# AFE_D.net
KiCad netlist of a schematic drawn in Altium Designer
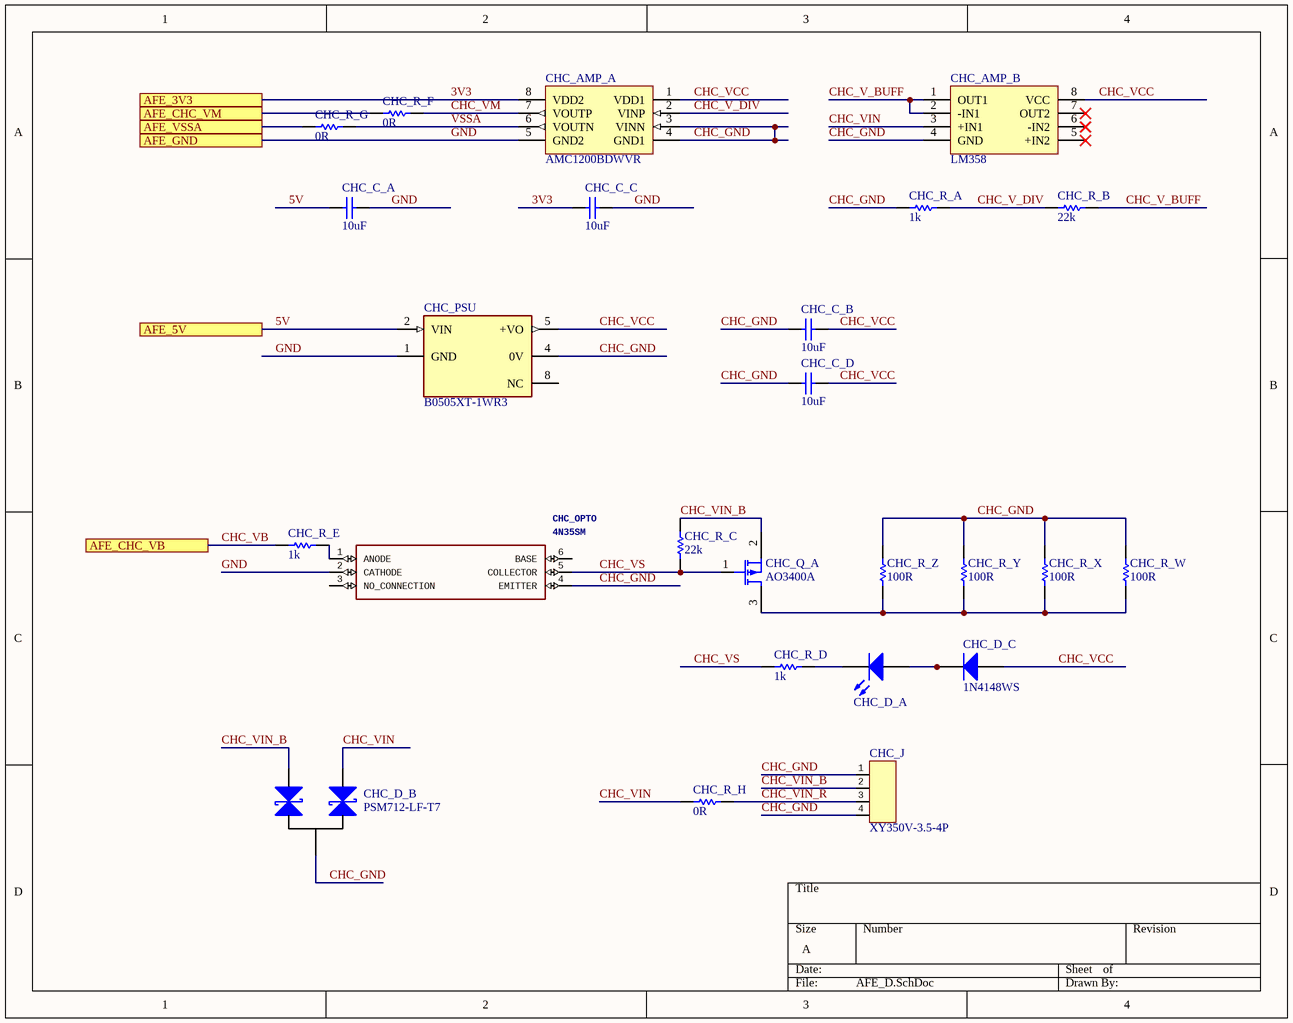
[diagram p0: AFE_D.SchDoc]

(export (version "E")
  (design (tool "Eeschema 10.0.6"))
  (components
    (comp (ref "CHC_AMP_A")
      (value "AMC1200BDWVR")
      (footprint "FOOTPRINTS:SOIC-8-P1.27-W7.5")
      (description "U - IC - 100KHz ISOLATION AMPLIFIER")
      (fields (field (name "LCSC PART #") "C79905"))
      (libsource (lib "JLC_PCB") (part "AMC1200BDWVR"))
    )
    (comp (ref "CHC_AMP_B")
      (value "LM358")
      (footprint "FOOTPRINTS:SOIC-8-P1.27-W3.5")
      (description "U - IC - OP AMP (DUAL)")
      (fields (field (name "LCSC PART #") "C63813"))
      (libsource (lib "JLC_PCB") (part "LMV358IDR"))
    )
    (comp (ref "CHC_C_A")
      (value "10uF")
      (footprint "C_0603")
      (description "C - CAPACITOR - MLCC - 10uF - 25V - 0603")
      (fields (field (name "LCSC PART #") "C96446") (field (name "Comment") "CL10A106MA8NRNC"))
      (libsource (lib "JLC_PCB") (part "CL10A106MA8NRNC"))
    )
    (comp (ref "CHC_C_B")
      (value "10uF")
      (footprint "C_0603")
      (description "C - CAPACITOR - MLCC - 10uF - 25V - 0603")
      (fields (field (name "LCSC PART #") "C96446") (field (name "Comment") "CL10A106MA8NRNC"))
      (libsource (lib "JLC_PCB") (part "CL10A106MA8NRNC"))
    )
    (comp (ref "CHC_C_C")
      (value "10uF")
      (footprint "C_0603")
      (description "C - CAPACITOR - MLCC - 10uF - 25V - 0603")
      (fields (field (name "LCSC PART #") "C96446") (field (name "Comment") "CL10A106MA8NRNC"))
      (libsource (lib "JLC_PCB") (part "CL10A106MA8NRNC"))
    )
    (comp (ref "CHC_C_D")
      (value "10uF")
      (footprint "C_0603")
      (description "C - CAPACITOR - MLCC - 10uF - 25V - 0603")
      (fields (field (name "LCSC PART #") "C96446") (field (name "Comment") "CL10A106MA8NRNC"))
      (libsource (lib "JLC_PCB") (part "CL10A106MA8NRNC"))
    )
    (comp (ref "CHC_D_A")
      (value "KT-0603R")
      (footprint "D_0603")
      (description "D - LED - 0603 - Red")
      (fields (field (name "LCSC PART #") "C2286"))
      (libsource (lib "JLC_PCB") (part "KT-0603R"))
    )
    (comp (ref "CHC_D_B")
      (value "PSM712-LF-T7")
      (footprint "TO-236AB")
      (description "D - DIODE - TVS x2 - 7.2V")
      (fields (field (name "LCSC PART #") "C32677"))
      (libsource (lib "JLC_PCB") (part "PSM712-LF-T7"))
    )
    (comp (ref "CHC_D_C")
      (value "1N4148WS")
      (footprint "SOD-323")
      (description "D - DIODE - FAST TRR - 100V - 150mA - 4ns")
      (fields (field (name "LCSC PART #") "C2128"))
      (libsource (lib "JLC_PCB") (part "1N4148WS"))
    )
    (comp (ref "CHC_J")
      (value "XY350V-3.5-4P")
      (footprint "XY350V-3.5-4P")
      (description "J - JACK - TERMINAL - 4P - RIGHT - MALE")
      (fields (field (name "LCSC PART #") "C557656"))
      (libsource (lib "JLC_PCB") (part "XY350V-3.5-4P"))
    )
    (comp (ref "CHC_OPTO")
      (value "4N35SM")
      (footprint "SOT254P916X508-6N")
      (description "Q - OPTOCOUPLER - 4170 V - 100% CTR")
      (fields (field (name "LCSC PART #") "C258228"))
      (libsource (lib "JLC_PCB") (part "4N35SM"))
    )
    (comp (ref "CHC_PSU")
      (value "B0505XT-1WR3")
      (footprint "CONV_B0512XT-1WR3")
      (description "T - Isolated Module DC DC Converter 5 -> 5V 200mA - DIP")
      (fields (field (name "LCSC PART #") "C19188495") (field (name "MF") "EVISUN"))
      (libsource (lib "JLC_PCB") (part "B0505XT-1WR3"))
    )
    (comp (ref "CHC_Q_A")
      (value "AO3400A")
      (footprint "TO-236AB")
      (description "Q - TRANSISTOR - MOSFET (P) - 20V - 3.4A - 0.26 Ohm")
      (fields (field (name "LCSC PART #") "C20917"))
      (libsource (lib "JLC_PCB") (part "AO3400A"))
    )
    (comp (ref "CHC_R_A")
      (value "1k")
      (footprint "R_0603")
      (description "R - RESISTOR - SMD - 1k - 1% - 0603")
      (fields (field (name "LCSC PART #") "C21190") (field (name "Comment") "0603WAF1001T5E"))
      (libsource (lib "JLC_PCB") (part "0603WAF1001T5E"))
    )
    (comp (ref "CHC_R_B")
      (value "22k")
      (footprint "R_0603")
      (description "R - RESISTOR - SMD - 22k - 1% - 0603")
      (fields (field (name "LCSC PART #") "C31850") (field (name "Comment") "0603WAF2202T5E"))
      (libsource (lib "JLC_PCB") (part "0603WAF2202T5E"))
    )
    (comp (ref "CHC_R_C")
      (value "22k")
      (footprint "R_0603")
      (description "R - RESISTOR - SMD - 22k - 1% - 0603")
      (fields (field (name "LCSC PART #") "C31850") (field (name "Comment") "0603WAF2202T5E"))
      (libsource (lib "JLC_PCB") (part "0603WAF2202T5E"))
    )
    (comp (ref "CHC_R_D")
      (value "1k")
      (footprint "R_0603")
      (description "R - RESISTOR - SMD - 1k - 1% - 0603")
      (fields (field (name "LCSC PART #") "C21190") (field (name "Comment") "0603WAF1001T5E"))
      (libsource (lib "JLC_PCB") (part "0603WAF1001T5E"))
    )
    (comp (ref "CHC_R_E")
      (value "1k")
      (footprint "R_0603")
      (description "R - RESISTOR - SMD - 1k - 1% - 0603")
      (fields (field (name "LCSC PART #") "C21190") (field (name "Comment") "0603WAF1001T5E"))
      (libsource (lib "JLC_PCB") (part "0603WAF1001T5E"))
    )
    (comp (ref "CHC_R_F")
      (value "0R")
      (footprint "R_0603")
      (description "R - RESISTOR - SMD - 0R - 1% - 0603")
      (fields (field (name "LCSC PART #") "C21189") (field (name "Comment") "0603WAF0000T5E"))
      (libsource (lib "JLC_PCB") (part "0603WAF0000T5E"))
    )
    (comp (ref "CHC_R_G")
      (value "0R")
      (footprint "R_0603")
      (description "R - RESISTOR - SMD - 0R - 1% - 0603")
      (fields (field (name "LCSC PART #") "C21189") (field (name "Comment") "0603WAF0000T5E"))
      (libsource (lib "JLC_PCB") (part "0603WAF0000T5E"))
    )
    (comp (ref "CHC_R_H")
      (value "0R")
      (footprint "R_0603")
      (description "R - RESISTOR - SMD - 0R - 1% - 0603")
      (fields (field (name "LCSC PART #") "C21189") (field (name "Comment") "0603WAF0000T5E"))
      (libsource (lib "JLC_PCB") (part "0603WAF0000T5E"))
    )
    (comp (ref "CHC_R_W")
      (value "100R")
      (footprint "R_1206")
      (description "R - RESISTOR - SMD - 100R - 1% - 1206")
      (fields (field (name "LCSC PART #") "C17901") (field (name "Comment") "1206W4F1000T5E"))
      (libsource (lib "JLC_PCB") (part "1206W4F1000T5E"))
    )
    (comp (ref "CHC_R_X")
      (value "100R")
      (footprint "R_1206")
      (description "R - RESISTOR - SMD - 100R - 1% - 1206")
      (fields (field (name "LCSC PART #") "C17901") (field (name "Comment") "1206W4F1000T5E"))
      (libsource (lib "JLC_PCB") (part "1206W4F1000T5E"))
    )
    (comp (ref "CHC_R_Y")
      (value "100R")
      (footprint "R_1206")
      (description "R - RESISTOR - SMD - 100R - 1% - 1206")
      (fields (field (name "LCSC PART #") "C17901") (field (name "Comment") "1206W4F1000T5E"))
      (libsource (lib "JLC_PCB") (part "1206W4F1000T5E"))
    )
    (comp (ref "CHC_R_Z")
      (value "100R")
      (footprint "R_1206")
      (description "R - RESISTOR - SMD - 100R - 1% - 1206")
      (fields (field (name "LCSC PART #") "C17901") (field (name "Comment") "1206W4F1000T5E"))
      (libsource (lib "JLC_PCB") (part "1206W4F1000T5E"))
    )
  )
  (nets
    (net (code "1") (name "/3V3") (class "Default")
      (node (ref "CHC_AMP_A") (pin "8") (pinfunction "VDD2_8") (pintype "passive"))
      (node (ref "CHC_C_C") (pin "2") (pinfunction "2_2") (pintype "passive"))
    )
    (net (code "2") (name "/5V") (class "Default")
      (node (ref "CHC_C_A") (pin "2") (pinfunction "2_2") (pintype "passive"))
      (node (ref "CHC_PSU") (pin "2") (pinfunction "VIN_2") (pintype "input"))
    )
    (net (code "3") (name "/AFE_CHC_VM") (class "Default")
      (node (ref "CHC_R_F") (pin "1") (pinfunction "1_1") (pintype "passive"))
    )
    (net (code "4") (name "/AFE_VSSA") (class "Default")
      (node (ref "CHC_R_G") (pin "1") (pinfunction "1_1") (pintype "passive"))
    )
    (net (code "5") (name "/CHC_GND") (class "Default")
      (node (ref "CHC_AMP_A") (pin "3") (pinfunction "VINN_3") (pintype "input"))
      (node (ref "CHC_AMP_A") (pin "4") (pinfunction "GND1_4") (pintype "power_in"))
      (node (ref "CHC_AMP_B") (pin "4") (pinfunction "GND_4") (pintype "passive"))
      (node (ref "CHC_C_B") (pin "2") (pinfunction "2_2") (pintype "passive"))
      (node (ref "CHC_C_D") (pin "2") (pinfunction "2_2") (pintype "passive"))
      (node (ref "CHC_D_B") (pin "3") (pinfunction "A_3") (pintype "passive"))
      (node (ref "CHC_J") (pin "1") (pinfunction "1_1") (pintype "passive"))
      (node (ref "CHC_J") (pin "4") (pinfunction "4_4") (pintype "passive"))
      (node (ref "CHC_OPTO") (pin "4") (pinfunction "EMITTER_4") (pintype "bidirectional"))
      (node (ref "CHC_PSU") (pin "4") (pinfunction "0V_4") (pintype "passive"))
      (node (ref "CHC_R_A") (pin "1") (pinfunction "1_1") (pintype "passive"))
      (node (ref "CHC_R_W") (pin "1") (pinfunction "1_1") (pintype "passive"))
      (node (ref "CHC_R_X") (pin "1") (pinfunction "1_1") (pintype "passive"))
      (node (ref "CHC_R_Y") (pin "1") (pinfunction "1_1") (pintype "passive"))
      (node (ref "CHC_R_Z") (pin "1") (pinfunction "1_1") (pintype "passive"))
    )
    (net (code "6") (name "/CHC_VB") (class "Default")
      (node (ref "CHC_R_E") (pin "1") (pinfunction "1_1") (pintype "passive"))
    )
    (net (code "7") (name "/CHC_VCC") (class "Default")
      (node (ref "CHC_AMP_A") (pin "1") (pinfunction "VDD1_1") (pintype "passive"))
      (node (ref "CHC_AMP_B") (pin "8") (pinfunction "VCC_8") (pintype "passive"))
      (node (ref "CHC_C_B") (pin "1") (pinfunction "1_1") (pintype "passive"))
      (node (ref "CHC_C_D") (pin "1") (pinfunction "1_1") (pintype "passive"))
      (node (ref "CHC_D_C") (pin "2") (pinfunction "A_2") (pintype "passive"))
      (node (ref "CHC_PSU") (pin "5") (pinfunction "+VO_5") (pintype "output"))
    )
    (net (code "8") (name "/CHC_VIN") (class "Default")
      (node (ref "CHC_AMP_B") (pin "3") (pinfunction "+IN1_3") (pintype "passive"))
      (node (ref "CHC_D_B") (pin "2") (pinfunction "K_2") (pintype "passive"))
      (node (ref "CHC_R_H") (pin "1") (pinfunction "1_1") (pintype "passive"))
    )
    (net (code "9") (name "/CHC_VIN_B") (class "Default")
      (node (ref "CHC_D_B") (pin "1") (pinfunction "K_1") (pintype "passive"))
      (node (ref "CHC_J") (pin "2") (pinfunction "2_2") (pintype "passive"))
      (node (ref "CHC_Q_A") (pin "2") (pinfunction "S_2") (pintype "passive"))
      (node (ref "CHC_R_C") (pin "2") (pinfunction "2_2") (pintype "passive"))
    )
    (net (code "10") (name "/CHC_VIN_R") (class "Default")
      (node (ref "CHC_J") (pin "3") (pinfunction "3_3") (pintype "passive"))
      (node (ref "CHC_R_H") (pin "2") (pinfunction "2_2") (pintype "passive"))
    )
    (net (code "11") (name "/CHC_VM") (class "Default")
      (node (ref "CHC_AMP_A") (pin "7") (pinfunction "VOUTP_7") (pintype "output"))
      (node (ref "CHC_R_F") (pin "2") (pinfunction "2_2") (pintype "passive"))
    )
    (net (code "12") (name "/CHC_VS") (class "Default")
      (node (ref "CHC_OPTO") (pin "5") (pinfunction "COLLECTOR_5") (pintype "bidirectional"))
      (node (ref "CHC_Q_A") (pin "1") (pinfunction "G_1") (pintype "passive"))
      (node (ref "CHC_R_C") (pin "1") (pinfunction "1_1") (pintype "passive"))
      (node (ref "CHC_R_D") (pin "1") (pinfunction "1_1") (pintype "passive"))
    )
    (net (code "13") (name "/CHC_V_BUFF") (class "Default")
      (node (ref "CHC_AMP_B") (pin "1") (pinfunction "OUT1_1") (pintype "passive"))
      (node (ref "CHC_AMP_B") (pin "2") (pinfunction "-IN1_2") (pintype "passive"))
      (node (ref "CHC_R_B") (pin "2") (pinfunction "2_2") (pintype "passive"))
    )
    (net (code "14") (name "/CHC_V_DIV") (class "Default")
      (node (ref "CHC_AMP_A") (pin "2") (pinfunction "VINP_2") (pintype "input"))
      (node (ref "CHC_R_A") (pin "2") (pinfunction "2_2") (pintype "passive"))
      (node (ref "CHC_R_B") (pin "1") (pinfunction "1_1") (pintype "passive"))
    )
    (net (code "15") (name "/GND") (class "Default")
      (node (ref "CHC_AMP_A") (pin "5") (pinfunction "GND2_5") (pintype "power_in"))
      (node (ref "CHC_C_A") (pin "1") (pinfunction "1_1") (pintype "passive"))
      (node (ref "CHC_C_C") (pin "1") (pinfunction "1_1") (pintype "passive"))
      (node (ref "CHC_OPTO") (pin "2") (pinfunction "CATHODE_2") (pintype "bidirectional"))
      (node (ref "CHC_PSU") (pin "1") (pinfunction "GND_1") (pintype "power_in"))
    )
    (net (code "16") (name "/VSSA") (class "Default")
      (node (ref "CHC_AMP_A") (pin "6") (pinfunction "VOUTN_6") (pintype "output"))
      (node (ref "CHC_R_G") (pin "2") (pinfunction "2_2") (pintype "passive"))
    )
    (net (code "17") (name "Net-(CHC_D_A-A)") (class "Default")
      (node (ref "CHC_D_A") (pin "2") (pinfunction "A_2") (pintype "passive"))
      (node (ref "CHC_D_C") (pin "1") (pinfunction "K_1") (pintype "passive"))
    )
    (net (code "18") (name "Net-(CHC_D_A-K)") (class "Default")
      (node (ref "CHC_D_A") (pin "1") (pinfunction "K_1") (pintype "passive"))
      (node (ref "CHC_R_D") (pin "2") (pinfunction "2_2") (pintype "passive"))
    )
    (net (code "19") (name "Net-(CHC_OPTO-ANODE)") (class "Default")
      (node (ref "CHC_OPTO") (pin "1") (pinfunction "ANODE_1") (pintype "bidirectional"))
      (node (ref "CHC_R_E") (pin "2") (pinfunction "2_2") (pintype "passive"))
    )
    (net (code "20") (name "Net-(CHC_Q_A-D)") (class "Default")
      (node (ref "CHC_Q_A") (pin "3") (pinfunction "D_3") (pintype "passive"))
      (node (ref "CHC_R_W") (pin "2") (pinfunction "2_2") (pintype "passive"))
      (node (ref "CHC_R_X") (pin "2") (pinfunction "2_2") (pintype "passive"))
      (node (ref "CHC_R_Y") (pin "2") (pinfunction "2_2") (pintype "passive"))
      (node (ref "CHC_R_Z") (pin "2") (pinfunction "2_2") (pintype "passive"))
    )
    (net (code "21") (name "unconnected-(CHC_AMP_B-+IN2-Pad5)") (class "Default")
      (node (ref "CHC_AMP_B") (pin "5") (pinfunction "+IN2_5") (pintype "passive+no_connect"))
    )
    (net (code "22") (name "unconnected-(CHC_AMP_B--IN2-Pad6)") (class "Default")
      (node (ref "CHC_AMP_B") (pin "6") (pinfunction "-IN2_6") (pintype "passive+no_connect"))
    )
    (net (code "23") (name "unconnected-(CHC_AMP_B-OUT2-Pad7)") (class "Default")
      (node (ref "CHC_AMP_B") (pin "7") (pinfunction "OUT2_7") (pintype "passive+no_connect"))
    )
    (net (code "24") (name "unconnected-(CHC_OPTO-BASE-Pad6)") (class "Default")
      (node (ref "CHC_OPTO") (pin "6") (pinfunction "BASE_6") (pintype "bidirectional"))
    )
    (net (code "25") (name "unconnected-(CHC_OPTO-NO_CONNECTION-Pad3)") (class "Default")
      (node (ref "CHC_OPTO") (pin "3") (pinfunction "NO_CONNECTION_3") (pintype "bidirectional"))
    )
    (net (code "26") (name "unconnected-(CHC_PSU-NC-Pad8)") (class "Default")
      (node (ref "CHC_PSU") (pin "8") (pinfunction "NC_8") (pintype "passive"))
    )
  )
)
